# fet-switch-smd-16mm-mk-1_0.net
KiCad netlist of a schematic drawn in EAGLE
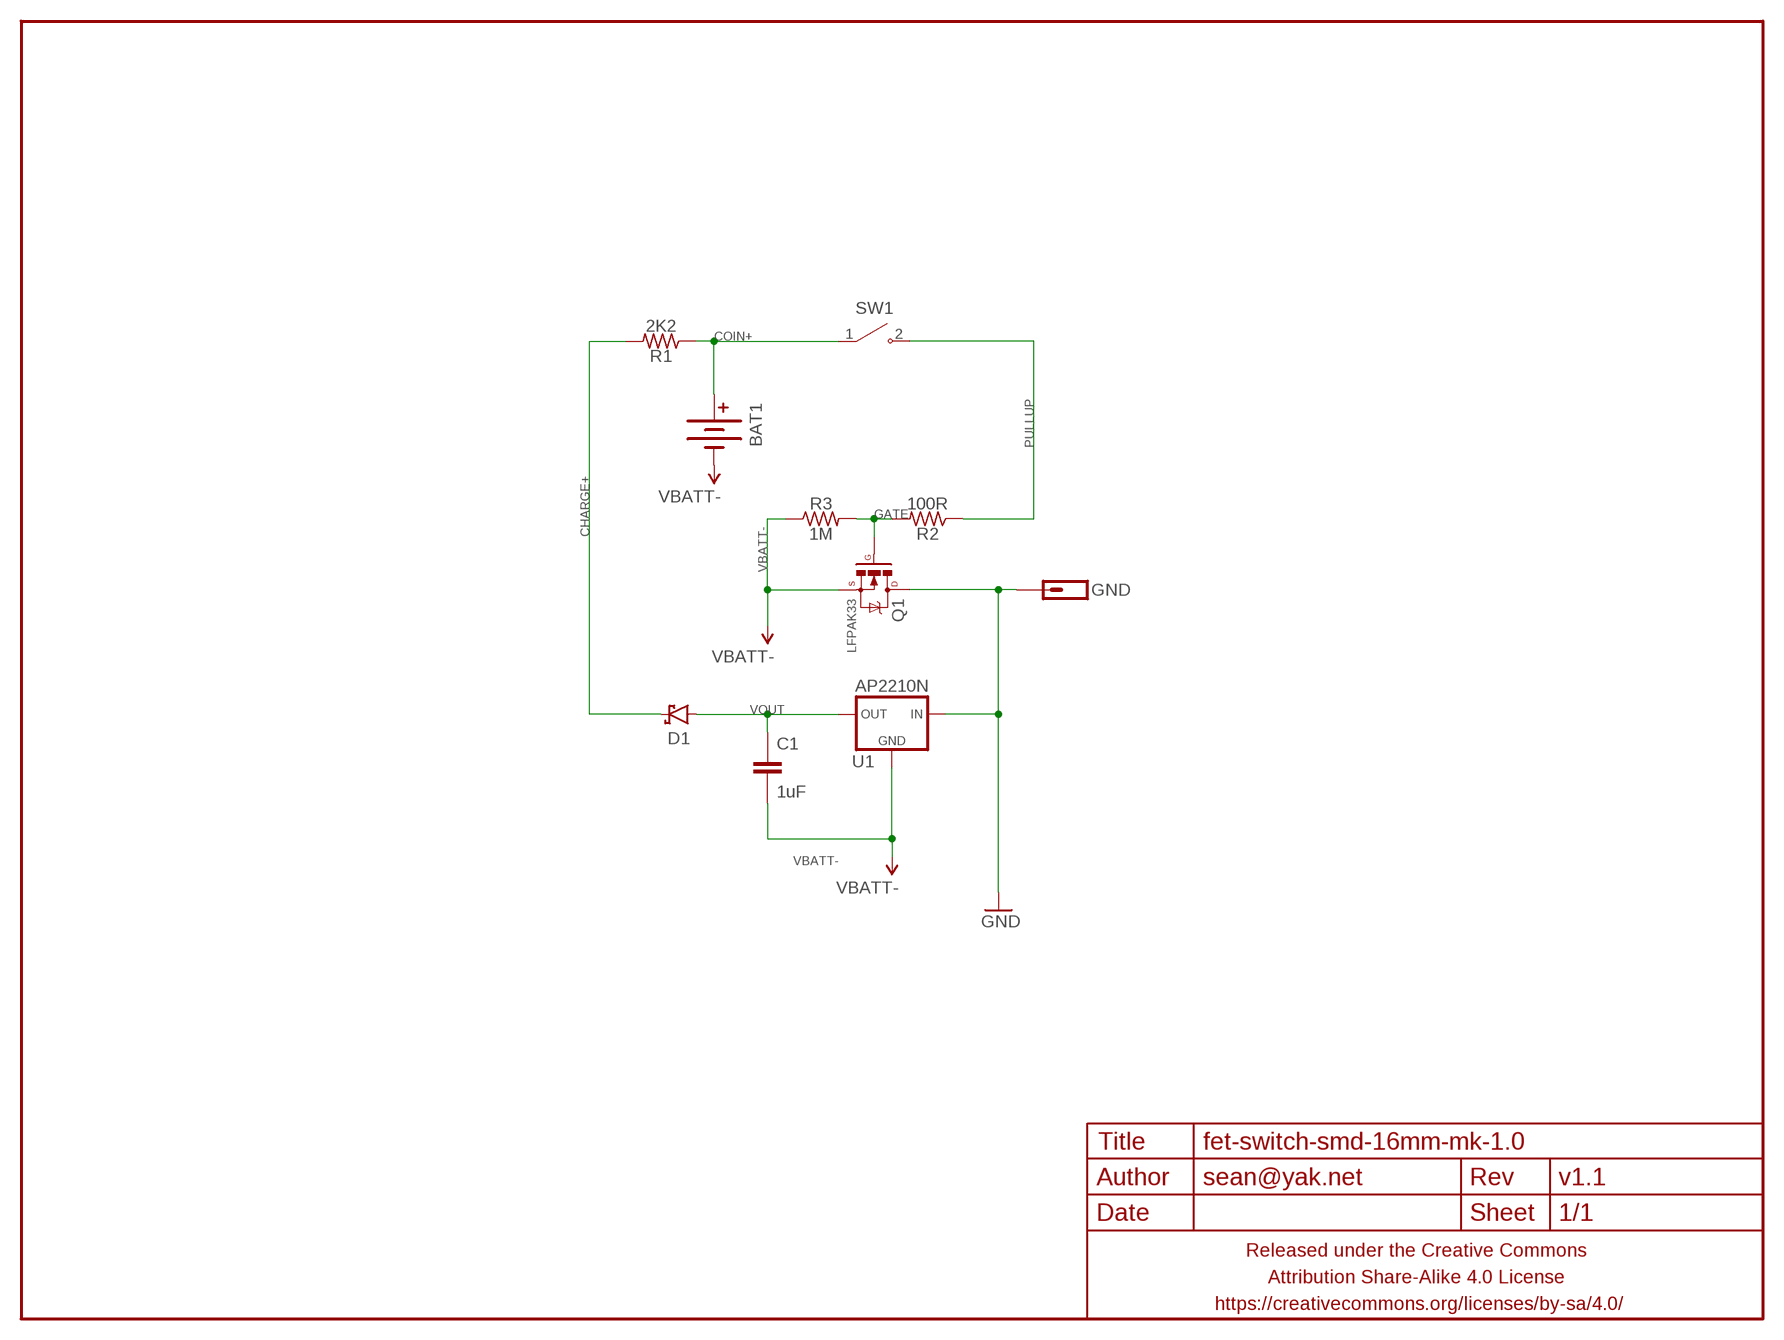
[diagram p0: schematic, sheet 1]

(export (version "E")
  (design (tool "Eeschema 10.0.6"))
  (components
    (comp (ref "BAT1")
      (value "BATTERYML414")
      (footprint "eagle-import:BATTCON_4.8MM")
      (libsource (lib "eagle-import") (part "BATTERYML414"))
    )
    (comp (ref "C1")
      (value "1uF")
      (footprint "eagle-import:C0402")
      (libsource (lib "eagle-import") (part "CAPACITOR-CERAMICC0402"))
    )
    (comp (ref "D1")
      (value "DIODE-SCHOTTKYSOD323")
      (footprint "eagle-import:SOD323-SCHOTTKY")
      (libsource (lib "eagle-import") (part "DIODE-SCHOTTKYSOD323"))
    )
    (comp (ref "FRAME1")
      (value "FRAME-LETTERNO_PACKAGE")
      (footprint "eagle-import:DUMMY")
      (fields
        (field (name "DESIGNER") "sean@yak.net")
        (field (name "VERSION") "v1.1")
        (field (name "DESIGNER_1") "sean@yak.net")
        (field (name "VERSION_1") "v1.1")
      )
      (libsource (lib "eagle-import") (part "FRAME-LETTERNO_PACKAGE"))
    )
    (comp (ref "GND")
      (value "M01NOT-A-VIA-NOPE")
      (footprint "eagle-import:1X01_NOSILK_NOSTOP")
      (libsource (lib "eagle-import") (part "M01NOT-A-VIA-NOPE"))
    )
    (comp (ref "Q1")
      (value "LFPAK33")
      (footprint "eagle-import:LFPAK33")
      (libsource (lib "eagle-import") (part "MOSFET-NCHANNELLFPAK33"))
    )
    (comp (ref "R1")
      (value "2K2")
      (footprint "eagle-import:R0402")
      (libsource (lib "eagle-import") (part "RESISTORR0402"))
    )
    (comp (ref "R2")
      (value "100R")
      (footprint "eagle-import:R0402")
      (libsource (lib "eagle-import") (part "RESISTORR0402"))
    )
    (comp (ref "R3")
      (value "1M")
      (footprint "eagle-import:R0402")
      (libsource (lib "eagle-import") (part "RESISTORR0402"))
    )
    (comp (ref "SW1")
      (value "SWITCH-SPSTOMTEN-1288-SMD-NS")
      (footprint "eagle-import:OMTEN-1288-LESS2-NS")
      (libsource (lib "eagle-import") (part "SWITCH-SPSTOMTEN-1288-SMD-NS"))
    )
    (comp (ref "U1")
      (value "AP2210N")
      (footprint "eagle-import:SOT23-TIGHTER")
      (libsource (lib "eagle-import") (part "V_REG_78XXAP2210N-TIGHTER"))
    )
  )
  (nets
    (net (code "1") (name "/CHARGE+") (class "Default")
      (node (ref "D1") (pin "C") (pinfunction "C_C") (pintype "passive"))
      (node (ref "R1") (pin "2") (pinfunction "2_2") (pintype "passive"))
    )
    (net (code "2") (name "/COIN+") (class "Default")
      (node (ref "BAT1") (pin "A1") (pinfunction "+_A1") (pintype "power_in"))
      (node (ref "BAT1") (pin "A2") (pinfunction "+_A2") (pintype "power_in"))
      (node (ref "R1") (pin "1") (pinfunction "1_1") (pintype "passive"))
      (node (ref "SW1") (pin "1") (pinfunction "COM_1") (pintype "bidirectional"))
    )
    (net (code "3") (name "/GATE") (class "Default")
      (node (ref "Q1") (pin "4") (pinfunction "G_4") (pintype "passive"))
      (node (ref "R2") (pin "2") (pinfunction "2_2") (pintype "passive"))
      (node (ref "R3") (pin "2") (pinfunction "2_2") (pintype "passive"))
    )
    (net (code "4") (name "/PULLUP") (class "Default")
      (node (ref "R2") (pin "1") (pinfunction "1_1") (pintype "passive"))
      (node (ref "SW1") (pin "2") (pinfunction "NO_2") (pintype "bidirectional"))
    )
    (net (code "5") (name "/VOUT") (class "Default")
      (node (ref "C1") (pin "1") (pinfunction "1_1") (pintype "passive"))
      (node (ref "D1") (pin "A") (pinfunction "A_A") (pintype "passive"))
      (node (ref "U1") (pin "2") (pinfunction "OUT_2") (pintype "bidirectional"))
    )
    (net (code "6") (name "GND") (class "Default")
      (node (ref "GND") (pin "P$1") (pinfunction "1_P$1") (pintype "passive"))
      (node (ref "Q1") (pin "PAD") (pinfunction "D_PAD") (pintype "passive"))
      (node (ref "U1") (pin "3") (pinfunction "IN_3") (pintype "bidirectional"))
    )
    (net (code "7") (name "VBATT-") (class "Default")
      (node (ref "BAT1") (pin "-") (pinfunction "-_-") (pintype "power_in"))
      (node (ref "C1") (pin "2") (pinfunction "2_2") (pintype "passive"))
      (node (ref "Q1") (pin "1") (pinfunction "S_1") (pintype "passive"))
      (node (ref "Q1") (pin "2") (pinfunction "S_2") (pintype "passive"))
      (node (ref "Q1") (pin "3") (pinfunction "S_3") (pintype "passive"))
      (node (ref "R3") (pin "1") (pinfunction "1_1") (pintype "passive"))
      (node (ref "U1") (pin "1") (pinfunction "GND_1") (pintype "bidirectional"))
    )
  )
)
